# Hubbly.net
KiCad netlist of a schematic drawn in EasyEDA Pro
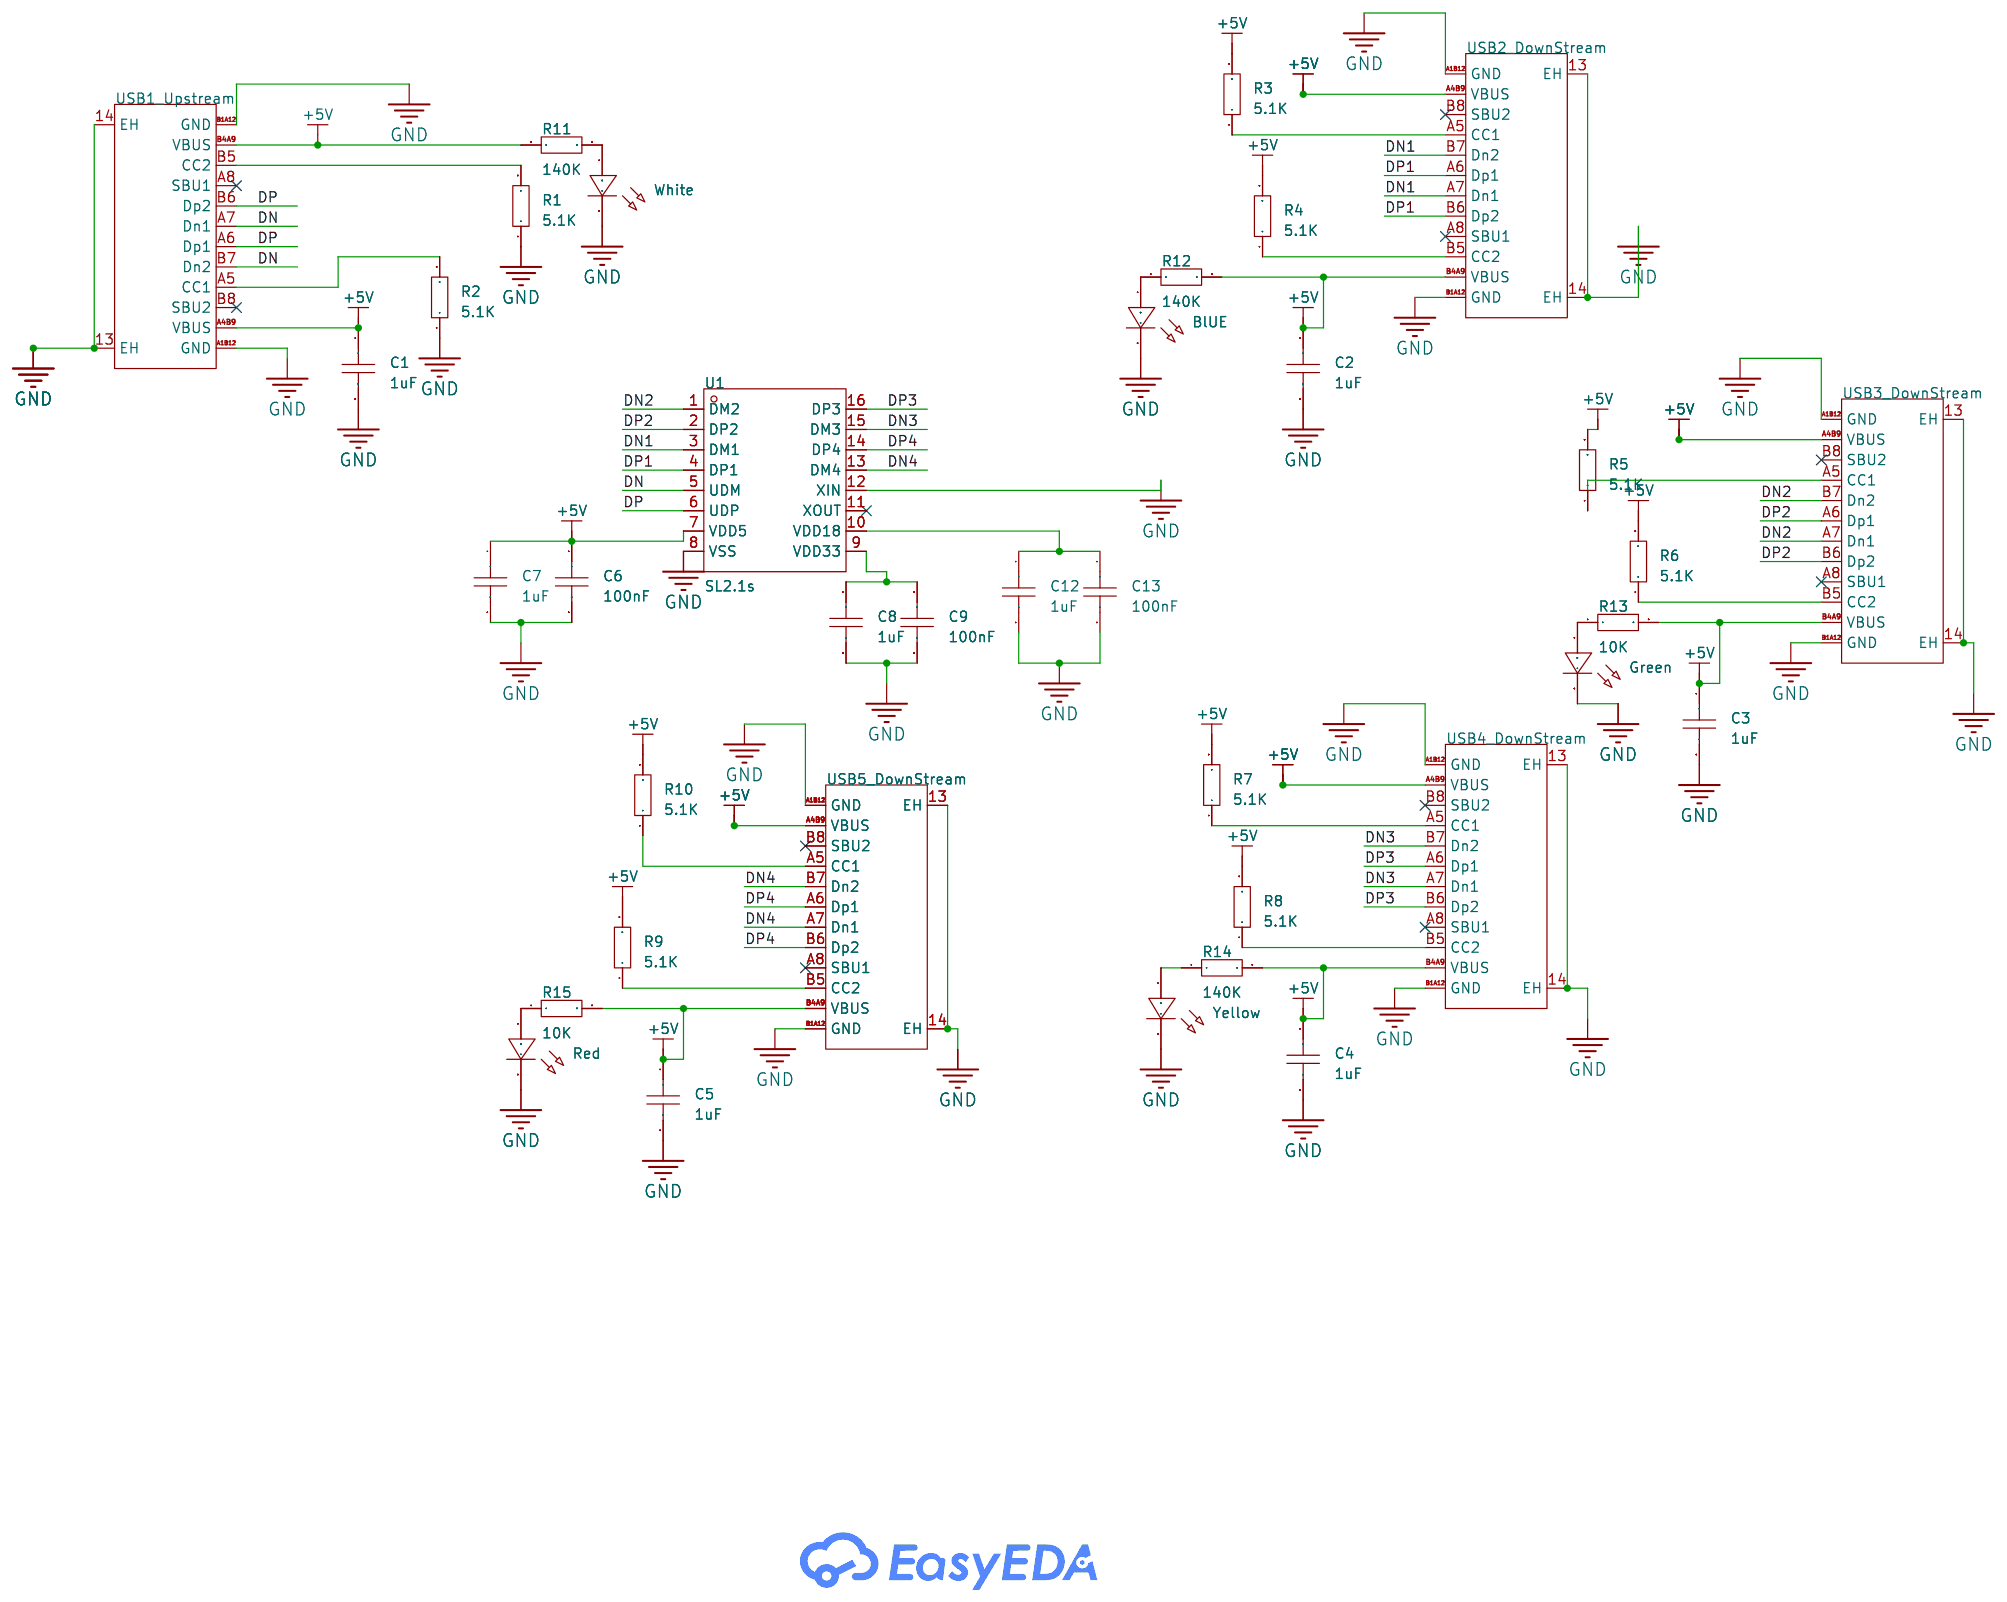
[diagram p0: schematic sheet]

(export (version "E")
  (design (tool "Eeschema 10.0.6"))
  (components
    (comp (ref "BlUE")
      (value "~")
      (footprint "easyedapro:LED-TH_BD5.0-P2.54-L-RD_WHITE")
      (libsource (lib "easyedapro") (part "LED_TH-B"))
    )
    (comp (ref "C1") (value "1uF") (footprint "easyedapro:C0603") (libsource (lib "easyedapro") (part "CAP")))
    (comp (ref "C2") (value "1uF") (footprint "easyedapro:C0603") (libsource (lib "easyedapro") (part "CAP")))
    (comp (ref "C3") (value "1uF") (footprint "easyedapro:C0603") (libsource (lib "easyedapro") (part "CAP")))
    (comp (ref "C4") (value "1uF") (footprint "easyedapro:C0603") (libsource (lib "easyedapro") (part "CAP")))
    (comp (ref "C5") (value "1uF") (footprint "easyedapro:C0603") (libsource (lib "easyedapro") (part "CAP")))
    (comp (ref "C6")
      (value "100nF")
      (footprint "easyedapro:C0603")
      (libsource (lib "easyedapro") (part "CAP"))
    )
    (comp (ref "C7") (value "1uF") (footprint "easyedapro:C0603") (libsource (lib "easyedapro") (part "CAP")))
    (comp (ref "C8") (value "1uF") (footprint "easyedapro:C0603") (libsource (lib "easyedapro") (part "CAP")))
    (comp (ref "C9")
      (value "100nF")
      (footprint "easyedapro:C0603")
      (libsource (lib "easyedapro") (part "CAP"))
    )
    (comp (ref "C12")
      (value "1uF")
      (footprint "easyedapro:C0603")
      (libsource (lib "easyedapro") (part "CAP"))
    )
    (comp (ref "C13")
      (value "100nF")
      (footprint "easyedapro:C0603")
      (libsource (lib "easyedapro") (part "CAP"))
    )
    (comp (ref "Green")
      (value "~")
      (footprint "easyedapro:LED-TH_BD5.0-P2.54-L-RD_WHITE")
      (libsource (lib "easyedapro") (part "LED_TH-B"))
    )
    (comp (ref "R1")
      (value "5.1K")
      (footprint "easyedapro:R0603")
      (libsource (lib "easyedapro") (part "Res"))
    )
    (comp (ref "R2")
      (value "5.1K")
      (footprint "easyedapro:R0603")
      (libsource (lib "easyedapro") (part "Res"))
    )
    (comp (ref "R3")
      (value "5.1K")
      (footprint "easyedapro:R0603")
      (libsource (lib "easyedapro") (part "Res"))
    )
    (comp (ref "R4")
      (value "5.1K")
      (footprint "easyedapro:R0603")
      (libsource (lib "easyedapro") (part "Res"))
    )
    (comp (ref "R5")
      (value "5.1K")
      (footprint "easyedapro:R0603")
      (libsource (lib "easyedapro") (part "Res"))
    )
    (comp (ref "R6")
      (value "5.1K")
      (footprint "easyedapro:R0603")
      (libsource (lib "easyedapro") (part "Res"))
    )
    (comp (ref "R7")
      (value "5.1K")
      (footprint "easyedapro:R0603")
      (libsource (lib "easyedapro") (part "Res"))
    )
    (comp (ref "R8")
      (value "5.1K")
      (footprint "easyedapro:R0603")
      (libsource (lib "easyedapro") (part "Res"))
    )
    (comp (ref "R9")
      (value "5.1K")
      (footprint "easyedapro:R0603")
      (libsource (lib "easyedapro") (part "Res"))
    )
    (comp (ref "R10")
      (value "5.1K")
      (footprint "easyedapro:R0603")
      (libsource (lib "easyedapro") (part "Res"))
    )
    (comp (ref "R11")
      (value "140K")
      (footprint "easyedapro:R0603")
      (libsource (lib "easyedapro") (part "Res"))
    )
    (comp (ref "R12")
      (value "140K")
      (footprint "easyedapro:R0603")
      (libsource (lib "easyedapro") (part "Res"))
    )
    (comp (ref "R13")
      (value "10K")
      (footprint "easyedapro:R0603")
      (libsource (lib "easyedapro") (part "Res"))
    )
    (comp (ref "R14")
      (value "140K")
      (footprint "easyedapro:R0603")
      (libsource (lib "easyedapro") (part "Res"))
    )
    (comp (ref "R15")
      (value "10K")
      (footprint "easyedapro:R0603")
      (libsource (lib "easyedapro") (part "Res"))
    )
    (comp (ref "Red")
      (value "~")
      (footprint "easyedapro:LED-TH_BD5.0-P2.54-L-RD_WHITE")
      (libsource (lib "easyedapro") (part "LED_TH-B"))
    )
    (comp (ref "U1")
      (value "SL2.1s")
      (footprint "easyedapro:SSOP-16_L4.6-W2.6-P0.53-LS4.0-BL")
      (fields (field (name "Manufacturer") "CoreChips(和芯润德)"))
      (libsource (lib "easyedapro") (part "SL2.1S"))
    )
    (comp (ref "USB1_Upstream")
      (value "TYPE-C 16PIN 2MD(073)")
      (footprint "easyedapro:USB-C-SMD_TYPE-C-16PIN-2MD-073")
      (fields (field (name "Manufacturer") "SHOU HAN(首韩)"))
      (libsource (lib "easyedapro") (part "TYPE-C 16PIN 2MD(073)"))
    )
    (comp (ref "USB2_DownStream")
      (value "TYPE-C 16PIN 2MD(073)")
      (footprint "easyedapro:USB-C-SMD_TYPE-C-16PIN-2MD-073")
      (fields (field (name "Manufacturer") "SHOU HAN(首韩)"))
      (libsource (lib "easyedapro") (part "TYPE-C 16PIN 2MD(073)"))
    )
    (comp (ref "USB3_DownStream")
      (value "TYPE-C 16PIN 2MD(073)")
      (footprint "easyedapro:USB-C-SMD_TYPE-C-16PIN-2MD-073")
      (fields (field (name "Manufacturer") "SHOU HAN(首韩)"))
      (libsource (lib "easyedapro") (part "TYPE-C 16PIN 2MD(073)"))
    )
    (comp (ref "USB4_DownStream")
      (value "TYPE-C 16PIN 2MD(073)")
      (footprint "easyedapro:USB-C-SMD_TYPE-C-16PIN-2MD-073")
      (fields (field (name "Manufacturer") "SHOU HAN(首韩)"))
      (libsource (lib "easyedapro") (part "TYPE-C 16PIN 2MD(073)"))
    )
    (comp (ref "USB5_DownStream")
      (value "TYPE-C 16PIN 2MD(073)")
      (footprint "easyedapro:USB-C-SMD_TYPE-C-16PIN-2MD-073")
      (fields (field (name "Manufacturer") "SHOU HAN(首韩)"))
      (libsource (lib "easyedapro") (part "TYPE-C 16PIN 2MD(073)"))
    )
    (comp (ref "White")
      (value "~")
      (footprint "easyedapro:LED-TH_BD5.0-P2.54-L-RD_WHITE")
      (libsource (lib "easyedapro") (part "LED_TH-B"))
    )
    (comp (ref "Yellow")
      (value "~")
      (footprint "easyedapro:LED-TH_BD5.0-P2.54-L-RD_WHITE")
      (libsource (lib "easyedapro") (part "LED_TH-B"))
    )
  )
  (nets
    (net (code "1") (name "+5V") (class "Default")
      (node (ref "C1") (pin "1") (pinfunction "1_1") (pintype "input"))
      (node (ref "C2") (pin "1") (pinfunction "1_1") (pintype "input"))
      (node (ref "C3") (pin "1") (pinfunction "1_1") (pintype "input"))
      (node (ref "C4") (pin "1") (pinfunction "1_1") (pintype "input"))
      (node (ref "C5") (pin "1") (pinfunction "1_1") (pintype "input"))
      (node (ref "C6") (pin "1") (pinfunction "1_1") (pintype "input"))
      (node (ref "C7") (pin "1") (pinfunction "1_1") (pintype "input"))
      (node (ref "R10") (pin "2") (pinfunction "2_2") (pintype "input"))
      (node (ref "R11") (pin "1") (pinfunction "1_1") (pintype "input"))
      (node (ref "R12") (pin "2") (pinfunction "2_2") (pintype "input"))
      (node (ref "R13") (pin "2") (pinfunction "2_2") (pintype "input"))
      (node (ref "R14") (pin "2") (pinfunction "2_2") (pintype "input"))
      (node (ref "R15") (pin "2") (pinfunction "2_2") (pintype "input"))
      (node (ref "R3") (pin "2") (pinfunction "2_2") (pintype "input"))
      (node (ref "R4") (pin "2") (pinfunction "2_2") (pintype "input"))
      (node (ref "R5") (pin "2") (pinfunction "2_2") (pintype "input"))
      (node (ref "R6") (pin "2") (pinfunction "2_2") (pintype "input"))
      (node (ref "R7") (pin "2") (pinfunction "2_2") (pintype "input"))
      (node (ref "R8") (pin "2") (pinfunction "2_2") (pintype "input"))
      (node (ref "R9") (pin "2") (pinfunction "2_2") (pintype "input"))
      (node (ref "U1") (pin "7") (pinfunction "VDD5_7") (pintype "unspecified"))
      (node (ref "USB1_Upstream") (pin "A4B9") (pinfunction "VBUS_A4B9") (pintype "unspecified"))
      (node (ref "USB1_Upstream") (pin "B4A9") (pinfunction "VBUS_B4A9") (pintype "unspecified"))
      (node (ref "USB2_DownStream") (pin "A4B9") (pinfunction "VBUS_A4B9") (pintype "unspecified"))
      (node (ref "USB2_DownStream") (pin "B4A9") (pinfunction "VBUS_B4A9") (pintype "unspecified"))
      (node (ref "USB3_DownStream") (pin "A4B9") (pinfunction "VBUS_A4B9") (pintype "unspecified"))
      (node (ref "USB3_DownStream") (pin "B4A9") (pinfunction "VBUS_B4A9") (pintype "unspecified"))
      (node (ref "USB4_DownStream") (pin "A4B9") (pinfunction "VBUS_A4B9") (pintype "unspecified"))
      (node (ref "USB4_DownStream") (pin "B4A9") (pinfunction "VBUS_B4A9") (pintype "unspecified"))
      (node (ref "USB5_DownStream") (pin "A4B9") (pinfunction "VBUS_A4B9") (pintype "unspecified"))
      (node (ref "USB5_DownStream") (pin "B4A9") (pinfunction "VBUS_B4A9") (pintype "unspecified"))
    )
    (net (code "2") (name "/DN") (class "Default")
      (node (ref "U1") (pin "5") (pinfunction "UDM_5") (pintype "unspecified"))
      (node (ref "USB1_Upstream") (pin "A7") (pinfunction "Dn1_A7") (pintype "unspecified"))
      (node (ref "USB1_Upstream") (pin "B7") (pinfunction "Dn2_B7") (pintype "unspecified"))
    )
    (net (code "3") (name "/DN1") (class "Default")
      (node (ref "U1") (pin "3") (pinfunction "DM1_3") (pintype "unspecified"))
      (node (ref "USB2_DownStream") (pin "A7") (pinfunction "Dn1_A7") (pintype "unspecified"))
      (node (ref "USB2_DownStream") (pin "B7") (pinfunction "Dn2_B7") (pintype "unspecified"))
    )
    (net (code "4") (name "/DN2") (class "Default")
      (node (ref "U1") (pin "1") (pinfunction "DM2_1") (pintype "unspecified"))
      (node (ref "USB3_DownStream") (pin "A7") (pinfunction "Dn1_A7") (pintype "unspecified"))
      (node (ref "USB3_DownStream") (pin "B7") (pinfunction "Dn2_B7") (pintype "unspecified"))
    )
    (net (code "5") (name "/DN3") (class "Default")
      (node (ref "U1") (pin "15") (pinfunction "DM3_15") (pintype "unspecified"))
      (node (ref "USB4_DownStream") (pin "A7") (pinfunction "Dn1_A7") (pintype "unspecified"))
      (node (ref "USB4_DownStream") (pin "B7") (pinfunction "Dn2_B7") (pintype "unspecified"))
    )
    (net (code "6") (name "/DN4") (class "Default")
      (node (ref "U1") (pin "13") (pinfunction "DM4_13") (pintype "unspecified"))
      (node (ref "USB5_DownStream") (pin "A7") (pinfunction "Dn1_A7") (pintype "unspecified"))
      (node (ref "USB5_DownStream") (pin "B7") (pinfunction "Dn2_B7") (pintype "unspecified"))
    )
    (net (code "7") (name "/DP") (class "Default")
      (node (ref "U1") (pin "6") (pinfunction "UDP_6") (pintype "unspecified"))
      (node (ref "USB1_Upstream") (pin "A6") (pinfunction "Dp1_A6") (pintype "unspecified"))
      (node (ref "USB1_Upstream") (pin "B6") (pinfunction "Dp2_B6") (pintype "unspecified"))
    )
    (net (code "8") (name "/DP1") (class "Default")
      (node (ref "U1") (pin "4") (pinfunction "DP1_4") (pintype "unspecified"))
      (node (ref "USB2_DownStream") (pin "A6") (pinfunction "Dp1_A6") (pintype "unspecified"))
      (node (ref "USB2_DownStream") (pin "B6") (pinfunction "Dp2_B6") (pintype "unspecified"))
    )
    (net (code "9") (name "/DP2") (class "Default")
      (node (ref "U1") (pin "2") (pinfunction "DP2_2") (pintype "unspecified"))
      (node (ref "USB3_DownStream") (pin "A6") (pinfunction "Dp1_A6") (pintype "unspecified"))
      (node (ref "USB3_DownStream") (pin "B6") (pinfunction "Dp2_B6") (pintype "unspecified"))
    )
    (net (code "10") (name "/DP3") (class "Default")
      (node (ref "U1") (pin "16") (pinfunction "DP3_16") (pintype "unspecified"))
      (node (ref "USB4_DownStream") (pin "A6") (pinfunction "Dp1_A6") (pintype "unspecified"))
      (node (ref "USB4_DownStream") (pin "B6") (pinfunction "Dp2_B6") (pintype "unspecified"))
    )
    (net (code "11") (name "/DP4") (class "Default")
      (node (ref "U1") (pin "14") (pinfunction "DP4_14") (pintype "unspecified"))
      (node (ref "USB5_DownStream") (pin "A6") (pinfunction "Dp1_A6") (pintype "unspecified"))
      (node (ref "USB5_DownStream") (pin "B6") (pinfunction "Dp2_B6") (pintype "unspecified"))
    )
    (net (code "12") (name "GND") (class "Default")
      (node (ref "BlUE") (pin "2") (pinfunction "A_2") (pintype "input"))
      (node (ref "C1") (pin "2") (pinfunction "2_2") (pintype "input"))
      (node (ref "C12") (pin "2") (pinfunction "2_2") (pintype "input"))
      (node (ref "C13") (pin "2") (pinfunction "2_2") (pintype "input"))
      (node (ref "C2") (pin "2") (pinfunction "2_2") (pintype "input"))
      (node (ref "C3") (pin "2") (pinfunction "2_2") (pintype "input"))
      (node (ref "C4") (pin "2") (pinfunction "2_2") (pintype "input"))
      (node (ref "C5") (pin "2") (pinfunction "2_2") (pintype "input"))
      (node (ref "C6") (pin "2") (pinfunction "2_2") (pintype "input"))
      (node (ref "C7") (pin "2") (pinfunction "2_2") (pintype "input"))
      (node (ref "C8") (pin "2") (pinfunction "2_2") (pintype "input"))
      (node (ref "C9") (pin "2") (pinfunction "2_2") (pintype "input"))
      (node (ref "Green") (pin "2") (pinfunction "A_2") (pintype "input"))
      (node (ref "R1") (pin "1") (pinfunction "1_1") (pintype "input"))
      (node (ref "R2") (pin "1") (pinfunction "1_1") (pintype "input"))
      (node (ref "Red") (pin "2") (pinfunction "A_2") (pintype "input"))
      (node (ref "U1") (pin "12") (pinfunction "XIN_12") (pintype "unspecified"))
      (node (ref "U1") (pin "8") (pinfunction "VSS_8") (pintype "unspecified"))
      (node (ref "USB1_Upstream") (pin "13") (pinfunction "EH_13") (pintype "unspecified"))
      (node (ref "USB1_Upstream") (pin "14") (pinfunction "EH_14") (pintype "unspecified"))
      (node (ref "USB1_Upstream") (pin "A1B12") (pinfunction "GND_A1B12") (pintype "unspecified"))
      (node (ref "USB1_Upstream") (pin "B1A12") (pinfunction "GND_B1A12") (pintype "unspecified"))
      (node (ref "USB2_DownStream") (pin "13") (pinfunction "EH_13") (pintype "unspecified"))
      (node (ref "USB2_DownStream") (pin "14") (pinfunction "EH_14") (pintype "unspecified"))
      (node (ref "USB2_DownStream") (pin "A1B12") (pinfunction "GND_A1B12") (pintype "unspecified"))
      (node (ref "USB2_DownStream") (pin "B1A12") (pinfunction "GND_B1A12") (pintype "unspecified"))
      (node (ref "USB3_DownStream") (pin "13") (pinfunction "EH_13") (pintype "unspecified"))
      (node (ref "USB3_DownStream") (pin "14") (pinfunction "EH_14") (pintype "unspecified"))
      (node (ref "USB3_DownStream") (pin "A1B12") (pinfunction "GND_A1B12") (pintype "unspecified"))
      (node (ref "USB3_DownStream") (pin "B1A12") (pinfunction "GND_B1A12") (pintype "unspecified"))
      (node (ref "USB4_DownStream") (pin "13") (pinfunction "EH_13") (pintype "unspecified"))
      (node (ref "USB4_DownStream") (pin "14") (pinfunction "EH_14") (pintype "unspecified"))
      (node (ref "USB4_DownStream") (pin "A1B12") (pinfunction "GND_A1B12") (pintype "unspecified"))
      (node (ref "USB4_DownStream") (pin "B1A12") (pinfunction "GND_B1A12") (pintype "unspecified"))
      (node (ref "USB5_DownStream") (pin "13") (pinfunction "EH_13") (pintype "unspecified"))
      (node (ref "USB5_DownStream") (pin "14") (pinfunction "EH_14") (pintype "unspecified"))
      (node (ref "USB5_DownStream") (pin "A1B12") (pinfunction "GND_A1B12") (pintype "unspecified"))
      (node (ref "USB5_DownStream") (pin "B1A12") (pinfunction "GND_B1A12") (pintype "unspecified"))
      (node (ref "White") (pin "2") (pinfunction "A_2") (pintype "input"))
      (node (ref "Yellow") (pin "2") (pinfunction "A_2") (pintype "input"))
    )
    (net (code "13") (name "Net-(BlUE-C)") (class "Default")
      (node (ref "BlUE") (pin "1") (pinfunction "C_1") (pintype "input"))
      (node (ref "R12") (pin "1") (pinfunction "1_1") (pintype "input"))
    )
    (net (code "14") (name "Net-(Green-C)") (class "Default")
      (node (ref "Green") (pin "1") (pinfunction "C_1") (pintype "input"))
      (node (ref "R13") (pin "1") (pinfunction "1_1") (pintype "input"))
    )
    (net (code "15") (name "Net-(Red-C)") (class "Default")
      (node (ref "R15") (pin "1") (pinfunction "1_1") (pintype "input"))
      (node (ref "Red") (pin "1") (pinfunction "C_1") (pintype "input"))
    )
    (net (code "16") (name "Net-(U1-VDD18)") (class "Default")
      (node (ref "C12") (pin "1") (pinfunction "1_1") (pintype "input"))
      (node (ref "C13") (pin "1") (pinfunction "1_1") (pintype "input"))
      (node (ref "U1") (pin "10") (pinfunction "VDD18_10") (pintype "unspecified"))
    )
    (net (code "17") (name "Net-(U1-VDD33)") (class "Default")
      (node (ref "C8") (pin "1") (pinfunction "1_1") (pintype "input"))
      (node (ref "C9") (pin "1") (pinfunction "1_1") (pintype "input"))
      (node (ref "U1") (pin "9") (pinfunction "VDD33_9") (pintype "unspecified"))
    )
    (net (code "18") (name "Net-(USB1_Upstream-CC1)") (class "Default")
      (node (ref "R2") (pin "2") (pinfunction "2_2") (pintype "input"))
      (node (ref "USB1_Upstream") (pin "A5") (pinfunction "CC1_A5") (pintype "unspecified"))
    )
    (net (code "19") (name "Net-(USB1_Upstream-CC2)") (class "Default")
      (node (ref "R1") (pin "2") (pinfunction "2_2") (pintype "input"))
      (node (ref "USB1_Upstream") (pin "B5") (pinfunction "CC2_B5") (pintype "unspecified"))
    )
    (net (code "20") (name "Net-(USB2_DownStream-CC1)") (class "Default")
      (node (ref "R3") (pin "1") (pinfunction "1_1") (pintype "input"))
      (node (ref "USB2_DownStream") (pin "A5") (pinfunction "CC1_A5") (pintype "unspecified"))
    )
    (net (code "21") (name "Net-(USB2_DownStream-CC2)") (class "Default")
      (node (ref "R4") (pin "1") (pinfunction "1_1") (pintype "input"))
      (node (ref "USB2_DownStream") (pin "B5") (pinfunction "CC2_B5") (pintype "unspecified"))
    )
    (net (code "22") (name "Net-(USB3_DownStream-CC1)") (class "Default")
      (node (ref "R5") (pin "1") (pinfunction "1_1") (pintype "input"))
      (node (ref "USB3_DownStream") (pin "A5") (pinfunction "CC1_A5") (pintype "unspecified"))
    )
    (net (code "23") (name "Net-(USB3_DownStream-CC2)") (class "Default")
      (node (ref "R6") (pin "1") (pinfunction "1_1") (pintype "input"))
      (node (ref "USB3_DownStream") (pin "B5") (pinfunction "CC2_B5") (pintype "unspecified"))
    )
    (net (code "24") (name "Net-(USB4_DownStream-CC1)") (class "Default")
      (node (ref "R7") (pin "1") (pinfunction "1_1") (pintype "input"))
      (node (ref "USB4_DownStream") (pin "A5") (pinfunction "CC1_A5") (pintype "unspecified"))
    )
    (net (code "25") (name "Net-(USB4_DownStream-CC2)") (class "Default")
      (node (ref "R8") (pin "1") (pinfunction "1_1") (pintype "input"))
      (node (ref "USB4_DownStream") (pin "B5") (pinfunction "CC2_B5") (pintype "unspecified"))
    )
    (net (code "26") (name "Net-(USB5_DownStream-CC1)") (class "Default")
      (node (ref "R10") (pin "1") (pinfunction "1_1") (pintype "input"))
      (node (ref "USB5_DownStream") (pin "A5") (pinfunction "CC1_A5") (pintype "unspecified"))
    )
    (net (code "27") (name "Net-(USB5_DownStream-CC2)") (class "Default")
      (node (ref "R9") (pin "1") (pinfunction "1_1") (pintype "input"))
      (node (ref "USB5_DownStream") (pin "B5") (pinfunction "CC2_B5") (pintype "unspecified"))
    )
    (net (code "28") (name "Net-(White-C)") (class "Default")
      (node (ref "R11") (pin "2") (pinfunction "2_2") (pintype "input"))
      (node (ref "White") (pin "1") (pinfunction "C_1") (pintype "input"))
    )
    (net (code "29") (name "Net-(Yellow-C)") (class "Default")
      (node (ref "R14") (pin "1") (pinfunction "1_1") (pintype "input"))
      (node (ref "Yellow") (pin "1") (pinfunction "C_1") (pintype "input"))
    )
    (net (code "30") (name "unconnected-(U1-XOUT-Pad11)") (class "Default")
      (node (ref "U1") (pin "11") (pinfunction "XOUT_11") (pintype "unspecified+no_connect"))
    )
    (net (code "31") (name "unconnected-(USB1_Upstream-SBU1-PadA8)") (class "Default")
      (node (ref "USB1_Upstream") (pin "A8") (pinfunction "SBU1_A8") (pintype "unspecified+no_connect"))
    )
    (net (code "32") (name "unconnected-(USB1_Upstream-SBU2-PadB8)") (class "Default")
      (node (ref "USB1_Upstream") (pin "B8") (pinfunction "SBU2_B8") (pintype "unspecified+no_connect"))
    )
    (net (code "33") (name "unconnected-(USB2_DownStream-SBU1-PadA8)") (class "Default")
      (node (ref "USB2_DownStream") (pin "A8") (pinfunction "SBU1_A8") (pintype "unspecified+no_connect"))
    )
    (net (code "34") (name "unconnected-(USB2_DownStream-SBU2-PadB8)") (class "Default")
      (node (ref "USB2_DownStream") (pin "B8") (pinfunction "SBU2_B8") (pintype "unspecified+no_connect"))
    )
    (net (code "35") (name "unconnected-(USB3_DownStream-SBU1-PadA8)") (class "Default")
      (node (ref "USB3_DownStream") (pin "A8") (pinfunction "SBU1_A8") (pintype "unspecified+no_connect"))
    )
    (net (code "36") (name "unconnected-(USB3_DownStream-SBU2-PadB8)") (class "Default")
      (node (ref "USB3_DownStream") (pin "B8") (pinfunction "SBU2_B8") (pintype "unspecified+no_connect"))
    )
    (net (code "37") (name "unconnected-(USB4_DownStream-SBU1-PadA8)") (class "Default")
      (node (ref "USB4_DownStream") (pin "A8") (pinfunction "SBU1_A8") (pintype "unspecified+no_connect"))
    )
    (net (code "38") (name "unconnected-(USB4_DownStream-SBU2-PadB8)") (class "Default")
      (node (ref "USB4_DownStream") (pin "B8") (pinfunction "SBU2_B8") (pintype "unspecified+no_connect"))
    )
    (net (code "39") (name "unconnected-(USB5_DownStream-SBU1-PadA8)") (class "Default")
      (node (ref "USB5_DownStream") (pin "A8") (pinfunction "SBU1_A8") (pintype "unspecified+no_connect"))
    )
    (net (code "40") (name "unconnected-(USB5_DownStream-SBU2-PadB8)") (class "Default")
      (node (ref "USB5_DownStream") (pin "B8") (pinfunction "SBU2_B8") (pintype "unspecified+no_connect"))
    )
  )
)
